# uC.net
KiCad netlist of a schematic drawn in Altium Designer
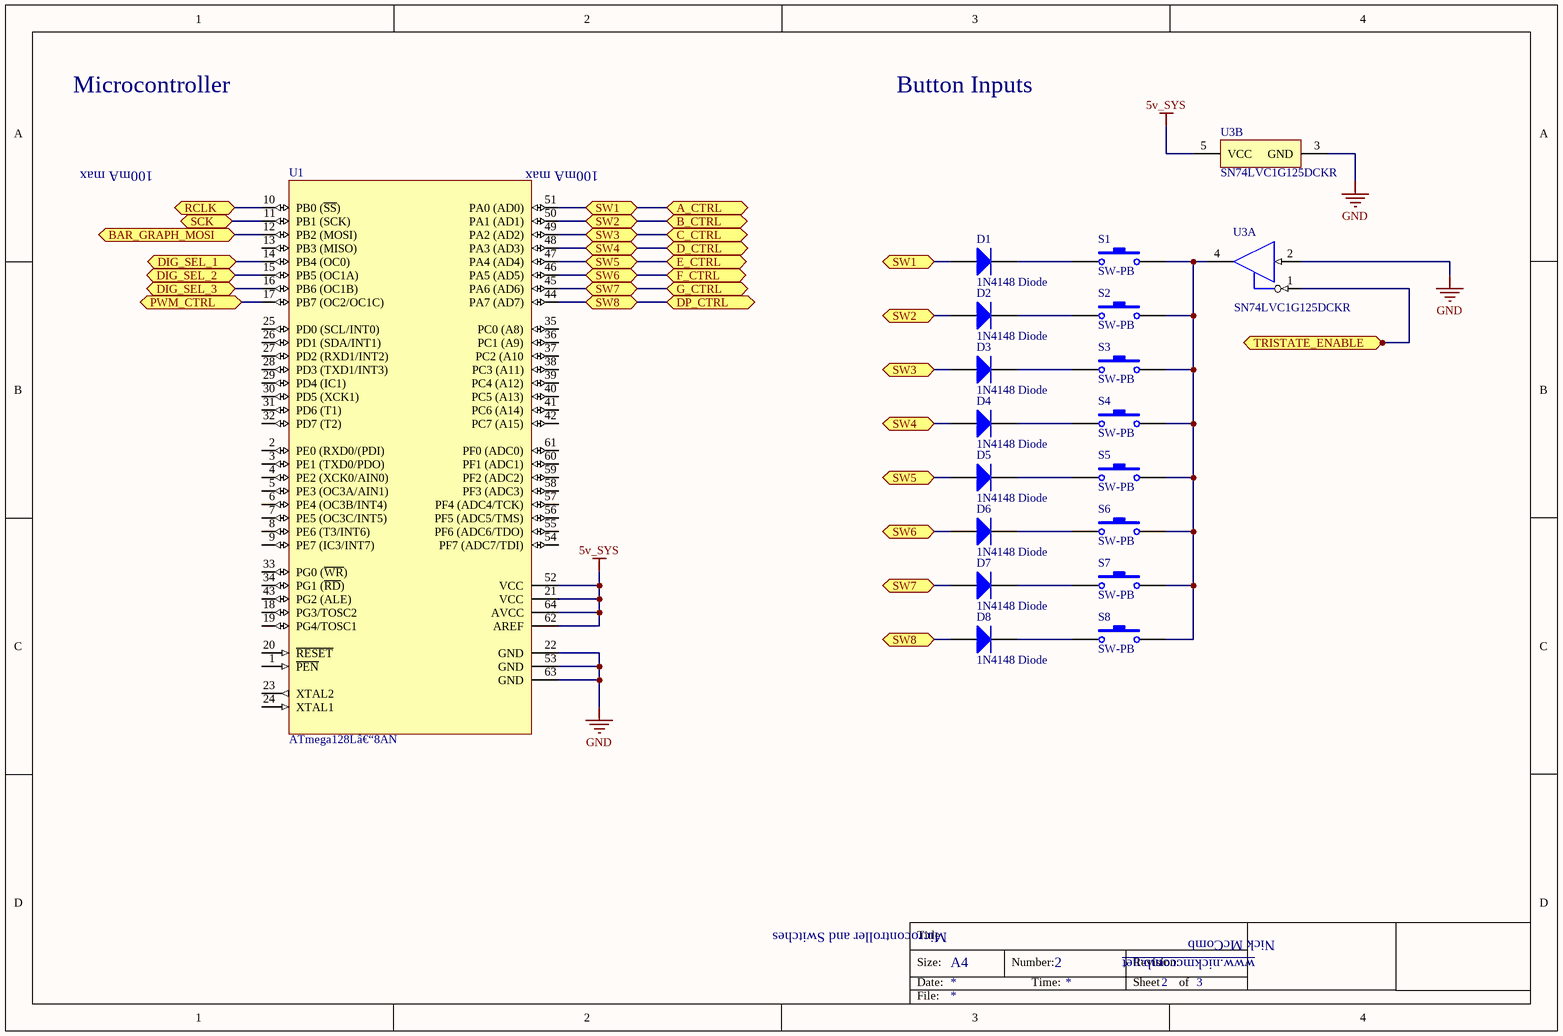
[diagram p0: uC.SchDoc]

(export (version "E")
  (design (tool "Eeschema 10.0.6"))
  (components
    (comp (ref "D1")
      (value "1N4148 Diode")
      (footprint "S01575 Diode")
      (description "Diode")
      (libsource (lib "lab2") (part "Diode"))
    )
    (comp (ref "D2")
      (value "1N4148 Diode")
      (footprint "S01575 Diode")
      (description "Diode")
      (libsource (lib "lab2") (part "Diode"))
    )
    (comp (ref "D3")
      (value "1N4148 Diode")
      (footprint "S01575 Diode")
      (description "Diode")
      (libsource (lib "lab2") (part "Diode"))
    )
    (comp (ref "D4")
      (value "1N4148 Diode")
      (footprint "S01575 Diode")
      (description "Diode")
      (libsource (lib "lab2") (part "Diode"))
    )
    (comp (ref "D5")
      (value "1N4148 Diode")
      (footprint "S01575 Diode")
      (description "Diode")
      (libsource (lib "lab2") (part "Diode"))
    )
    (comp (ref "D6")
      (value "1N4148 Diode")
      (footprint "S01575 Diode")
      (description "Diode")
      (libsource (lib "lab2") (part "Diode"))
    )
    (comp (ref "D7")
      (value "1N4148 Diode")
      (footprint "S01575 Diode")
      (description "Diode")
      (libsource (lib "lab2") (part "Diode"))
    )
    (comp (ref "D8")
      (value "1N4148 Diode")
      (footprint "S01575 Diode")
      (description "Diode")
      (libsource (lib "lab2") (part "Diode"))
    )
    (comp (ref "S1")
      (value "SW-PB")
      (footprint "SW-PB")
      (description "Switch")
      (libsource (lib "lab2") (part "SW-PB"))
    )
    (comp (ref "S2")
      (value "SW-PB")
      (footprint "SW-PB")
      (description "Switch")
      (libsource (lib "lab2") (part "SW-PB"))
    )
    (comp (ref "S3")
      (value "SW-PB")
      (footprint "SW-PB")
      (description "Switch")
      (libsource (lib "lab2") (part "SW-PB"))
    )
    (comp (ref "S4")
      (value "SW-PB")
      (footprint "SW-PB")
      (description "Switch")
      (libsource (lib "lab2") (part "SW-PB"))
    )
    (comp (ref "S5")
      (value "SW-PB")
      (footprint "SW-PB")
      (description "Switch")
      (libsource (lib "lab2") (part "SW-PB"))
    )
    (comp (ref "S6")
      (value "SW-PB")
      (footprint "SW-PB")
      (description "Switch")
      (libsource (lib "lab2") (part "SW-PB"))
    )
    (comp (ref "S7")
      (value "SW-PB")
      (footprint "SW-PB")
      (description "Switch")
      (libsource (lib "lab2") (part "SW-PB"))
    )
    (comp (ref "S8")
      (value "SW-PB")
      (footprint "SW-PB")
      (description "Switch")
      (libsource (lib "lab2") (part "SW-PB"))
    )
    (comp (ref "U1")
      (value "ATmega128Lâ€“8AN")
      (footprint "64A_M")
      (libsource (lib "Altium Content Vault") (part "MC-8B-AT64-SQ64"))
    )
    (comp (ref "U3")
      (value "SN74LVC1G125DCKR")
      (footprint "DCK0005A_M")
      (description "Single Bus Buffer Gate With 3-State Outputs, DCK0005A, LARGE T&R")
      (fields
        (field (name "GENERIC PART NUMBER") "SN74LVC1G125")
        (field (name "MANUFACTURER") "Texas Instruments")
      )
      (libsource (lib "Altium Content Vault") (part "TI-SN74AXXXX1X125-5"))
    )
  )
  (nets
    (net (code "1") (name "/A_CTRL") (class "Default")
      (node (ref "D1") (pin "3") (pinfunction "A_3") (pintype "passive"))
      (node (ref "U1") (pin "51") (pinfunction "PA0_(AD0)_51") (pintype "bidirectional"))
    )
    (net (code "2") (name "/BAR_GRAPH_MOSI") (class "Default")
      (node (ref "U1") (pin "12") (pinfunction "PB2_(MOSI)_12") (pintype "bidirectional"))
    )
    (net (code "3") (name "/B_CTRL") (class "Default")
      (node (ref "D2") (pin "3") (pinfunction "A_3") (pintype "passive"))
      (node (ref "U1") (pin "50") (pinfunction "PA1_(AD1)_50") (pintype "bidirectional"))
    )
    (net (code "4") (name "/C_CTRL") (class "Default")
      (node (ref "D3") (pin "3") (pinfunction "A_3") (pintype "passive"))
      (node (ref "U1") (pin "49") (pinfunction "PA2_(AD2)_49") (pintype "bidirectional"))
    )
    (net (code "5") (name "/DIG_SEL_1") (class "Default")
      (node (ref "U1") (pin "14") (pinfunction "PB4_(OC0)_14") (pintype "bidirectional"))
    )
    (net (code "6") (name "/DIG_SEL_2") (class "Default")
      (node (ref "U1") (pin "15") (pinfunction "PB5_(OC1A)_15") (pintype "bidirectional"))
    )
    (net (code "7") (name "/DIG_SEL_3") (class "Default")
      (node (ref "U1") (pin "16") (pinfunction "PB6_(OC1B)_16") (pintype "bidirectional"))
    )
    (net (code "8") (name "/DP_CTRL") (class "Default")
      (node (ref "D8") (pin "3") (pinfunction "A_3") (pintype "passive"))
      (node (ref "U1") (pin "44") (pinfunction "PA7_(AD7)_44") (pintype "bidirectional"))
    )
    (net (code "9") (name "/D_CTRL") (class "Default")
      (node (ref "D4") (pin "3") (pinfunction "A_3") (pintype "passive"))
      (node (ref "U1") (pin "48") (pinfunction "PA3_(AD3)_48") (pintype "bidirectional"))
    )
    (net (code "10") (name "/E_CTRL") (class "Default")
      (node (ref "D5") (pin "3") (pinfunction "A_3") (pintype "passive"))
      (node (ref "U1") (pin "47") (pinfunction "PA4_(AD4)_47") (pintype "bidirectional"))
    )
    (net (code "11") (name "/F_CTRL") (class "Default")
      (node (ref "D6") (pin "3") (pinfunction "A_3") (pintype "passive"))
      (node (ref "U1") (pin "46") (pinfunction "PA5_(AD5)_46") (pintype "bidirectional"))
    )
    (net (code "12") (name "/G_CTRL") (class "Default")
      (node (ref "D7") (pin "3") (pinfunction "A_3") (pintype "passive"))
      (node (ref "U1") (pin "45") (pinfunction "PA6_(AD6)_45") (pintype "bidirectional"))
    )
    (net (code "13") (name "/PWM_CTRL") (class "Default")
      (node (ref "U1") (pin "17") (pinfunction "PB7_(OC2/OC1C)_17") (pintype "bidirectional"))
    )
    (net (code "14") (name "/RCLK") (class "Default")
      (node (ref "U1") (pin "10") (pinfunction "PB0_(~{SS})_10") (pintype "bidirectional"))
    )
    (net (code "15") (name "/SCK") (class "Default")
      (node (ref "U1") (pin "11") (pinfunction "PB1_(SCK)_11") (pintype "bidirectional"))
    )
    (net (code "16") (name "/TRISTATE_ENABLE") (class "Default")
      (node (ref "U3") (pin "1") (pinfunction "~{OE}_1") (pintype "input"))
    )
    (net (code "17") (name "5v_SYS") (class "Default")
      (node (ref "U1") (pin "21") (pinfunction "VCC_21") (pintype "power_in"))
      (node (ref "U1") (pin "52") (pinfunction "VCC_52") (pintype "power_in"))
      (node (ref "U1") (pin "62") (pinfunction "AREF_62") (pintype "passive"))
      (node (ref "U1") (pin "64") (pinfunction "AVCC_64") (pintype "power_in"))
      (node (ref "U3") (pin "5") (pinfunction "VCC_5") (pintype "power_in"))
    )
    (net (code "18") (name "GND") (class "Default")
      (node (ref "U1") (pin "22") (pinfunction "GND_22") (pintype "power_in"))
      (node (ref "U1") (pin "53") (pinfunction "GND_53") (pintype "power_in"))
      (node (ref "U1") (pin "63") (pinfunction "GND_63") (pintype "power_in"))
      (node (ref "U3") (pin "2") (pinfunction "A_2") (pintype "input"))
      (node (ref "U3") (pin "3") (pinfunction "GND_3") (pintype "power_in"))
    )
    (net (code "19") (name "Net-(D1-K)") (class "Default")
      (node (ref "D1") (pin "1") (pinfunction "K_1") (pintype "passive"))
      (node (ref "S1") (pin "1") (pinfunction "1_1") (pintype "passive"))
    )
    (net (code "20") (name "Net-(D2-K)") (class "Default")
      (node (ref "D2") (pin "1") (pinfunction "K_1") (pintype "passive"))
      (node (ref "S2") (pin "1") (pinfunction "1_1") (pintype "passive"))
    )
    (net (code "21") (name "Net-(D3-K)") (class "Default")
      (node (ref "D3") (pin "1") (pinfunction "K_1") (pintype "passive"))
      (node (ref "S3") (pin "1") (pinfunction "1_1") (pintype "passive"))
    )
    (net (code "22") (name "Net-(D4-K)") (class "Default")
      (node (ref "D4") (pin "1") (pinfunction "K_1") (pintype "passive"))
      (node (ref "S4") (pin "1") (pinfunction "1_1") (pintype "passive"))
    )
    (net (code "23") (name "Net-(D5-K)") (class "Default")
      (node (ref "D5") (pin "1") (pinfunction "K_1") (pintype "passive"))
      (node (ref "S5") (pin "1") (pinfunction "1_1") (pintype "passive"))
    )
    (net (code "24") (name "Net-(D6-K)") (class "Default")
      (node (ref "D6") (pin "1") (pinfunction "K_1") (pintype "passive"))
      (node (ref "S6") (pin "1") (pinfunction "1_1") (pintype "passive"))
    )
    (net (code "25") (name "Net-(D7-K)") (class "Default")
      (node (ref "D7") (pin "1") (pinfunction "K_1") (pintype "passive"))
      (node (ref "S7") (pin "1") (pinfunction "1_1") (pintype "passive"))
    )
    (net (code "26") (name "Net-(D8-K)") (class "Default")
      (node (ref "D8") (pin "1") (pinfunction "K_1") (pintype "passive"))
      (node (ref "S8") (pin "1") (pinfunction "1_1") (pintype "passive"))
    )
    (net (code "27") (name "Net-(U3A-Y)") (class "Default")
      (node (ref "S1") (pin "2") (pinfunction "2_2") (pintype "passive"))
      (node (ref "S2") (pin "2") (pinfunction "2_2") (pintype "passive"))
      (node (ref "S3") (pin "2") (pinfunction "2_2") (pintype "passive"))
      (node (ref "S4") (pin "2") (pinfunction "2_2") (pintype "passive"))
      (node (ref "S5") (pin "2") (pinfunction "2_2") (pintype "passive"))
      (node (ref "S6") (pin "2") (pinfunction "2_2") (pintype "passive"))
      (node (ref "S7") (pin "2") (pinfunction "2_2") (pintype "passive"))
      (node (ref "S8") (pin "2") (pinfunction "2_2") (pintype "passive"))
      (node (ref "U3") (pin "4") (pinfunction "Y_4") (pintype "tri_state"))
    )
    (net (code "28") (name "unconnected-(U1-PB3_(MISO)-Pad13)") (class "Default")
      (node (ref "U1") (pin "13") (pinfunction "PB3_(MISO)_13") (pintype "bidirectional"))
    )
    (net (code "29") (name "unconnected-(U1-PC0_(A8)-Pad35)") (class "Default")
      (node (ref "U1") (pin "35") (pinfunction "PC0_(A8)_35") (pintype "bidirectional"))
    )
    (net (code "30") (name "unconnected-(U1-PC1_(A9)-Pad36)") (class "Default")
      (node (ref "U1") (pin "36") (pinfunction "PC1_(A9)_36") (pintype "bidirectional"))
    )
    (net (code "31") (name "unconnected-(U1-PC2_(A10-Pad37)") (class "Default")
      (node (ref "U1") (pin "37") (pinfunction "PC2_(A10_37") (pintype "bidirectional"))
    )
    (net (code "32") (name "unconnected-(U1-PC3_(A11)-Pad38)") (class "Default")
      (node (ref "U1") (pin "38") (pinfunction "PC3_(A11)_38") (pintype "bidirectional"))
    )
    (net (code "33") (name "unconnected-(U1-PC4_(A12)-Pad39)") (class "Default")
      (node (ref "U1") (pin "39") (pinfunction "PC4_(A12)_39") (pintype "bidirectional"))
    )
    (net (code "34") (name "unconnected-(U1-PC5_(A13)-Pad40)") (class "Default")
      (node (ref "U1") (pin "40") (pinfunction "PC5_(A13)_40") (pintype "bidirectional"))
    )
    (net (code "35") (name "unconnected-(U1-PC6_(A14)-Pad41)") (class "Default")
      (node (ref "U1") (pin "41") (pinfunction "PC6_(A14)_41") (pintype "bidirectional"))
    )
    (net (code "36") (name "unconnected-(U1-PC7_(A15)-Pad42)") (class "Default")
      (node (ref "U1") (pin "42") (pinfunction "PC7_(A15)_42") (pintype "bidirectional"))
    )
    (net (code "37") (name "unconnected-(U1-PD0_(SCL{slash}INT0)-Pad25)") (class "Default")
      (node (ref "U1") (pin "25") (pinfunction "PD0_(SCL/INT0)_25") (pintype "bidirectional"))
    )
    (net (code "38") (name "unconnected-(U1-PD1_(SDA{slash}INT1)-Pad26)") (class "Default")
      (node (ref "U1") (pin "26") (pinfunction "PD1_(SDA/INT1)_26") (pintype "bidirectional"))
    )
    (net (code "39") (name "unconnected-(U1-PD2_(RXD1{slash}INT2)-Pad27)") (class "Default")
      (node (ref "U1") (pin "27") (pinfunction "PD2_(RXD1/INT2)_27") (pintype "bidirectional"))
    )
    (net (code "40") (name "unconnected-(U1-PD3_(TXD1{slash}INT3)-Pad28)") (class "Default")
      (node (ref "U1") (pin "28") (pinfunction "PD3_(TXD1/INT3)_28") (pintype "bidirectional"))
    )
    (net (code "41") (name "unconnected-(U1-PD4_(IC1)-Pad29)") (class "Default")
      (node (ref "U1") (pin "29") (pinfunction "PD4_(IC1)_29") (pintype "bidirectional"))
    )
    (net (code "42") (name "unconnected-(U1-PD5_(XCK1)-Pad30)") (class "Default")
      (node (ref "U1") (pin "30") (pinfunction "PD5_(XCK1)_30") (pintype "bidirectional"))
    )
    (net (code "43") (name "unconnected-(U1-PD6_(T1)-Pad31)") (class "Default")
      (node (ref "U1") (pin "31") (pinfunction "PD6_(T1)_31") (pintype "bidirectional"))
    )
    (net (code "44") (name "unconnected-(U1-PD7_(T2)-Pad32)") (class "Default")
      (node (ref "U1") (pin "32") (pinfunction "PD7_(T2)_32") (pintype "bidirectional"))
    )
    (net (code "45") (name "unconnected-(U1-PE0_(RXD0{slash}(PDI)-Pad2)") (class "Default")
      (node (ref "U1") (pin "2") (pinfunction "PE0_(RXD0/(PDI)_2") (pintype "bidirectional"))
    )
    (net (code "46") (name "unconnected-(U1-PE1_(TXD0{slash}PDO)-Pad3)") (class "Default")
      (node (ref "U1") (pin "3") (pinfunction "PE1_(TXD0/PDO)_3") (pintype "bidirectional"))
    )
    (net (code "47") (name "unconnected-(U1-PE2_(XCK0{slash}AIN0)-Pad4)") (class "Default")
      (node (ref "U1") (pin "4") (pinfunction "PE2_(XCK0/AIN0)_4") (pintype "bidirectional"))
    )
    (net (code "48") (name "unconnected-(U1-PE3_(OC3A{slash}AIN1)-Pad5)") (class "Default")
      (node (ref "U1") (pin "5") (pinfunction "PE3_(OC3A/AIN1)_5") (pintype "bidirectional"))
    )
    (net (code "49") (name "unconnected-(U1-PE4_(OC3B{slash}INT4)-Pad6)") (class "Default")
      (node (ref "U1") (pin "6") (pinfunction "PE4_(OC3B/INT4)_6") (pintype "bidirectional"))
    )
    (net (code "50") (name "unconnected-(U1-PE5_(OC3C{slash}INT5)-Pad7)") (class "Default")
      (node (ref "U1") (pin "7") (pinfunction "PE5_(OC3C/INT5)_7") (pintype "bidirectional"))
    )
    (net (code "51") (name "unconnected-(U1-PE6_(T3{slash}INT6)-Pad8)") (class "Default")
      (node (ref "U1") (pin "8") (pinfunction "PE6_(T3/INT6)_8") (pintype "bidirectional"))
    )
    (net (code "52") (name "unconnected-(U1-PE7_(IC3{slash}INT7)-Pad9)") (class "Default")
      (node (ref "U1") (pin "9") (pinfunction "PE7_(IC3/INT7)_9") (pintype "bidirectional"))
    )
    (net (code "53") (name "unconnected-(U1-PF0_(ADC0)-Pad61)") (class "Default")
      (node (ref "U1") (pin "61") (pinfunction "PF0_(ADC0)_61") (pintype "bidirectional"))
    )
    (net (code "54") (name "unconnected-(U1-PF1_(ADC1)-Pad60)") (class "Default")
      (node (ref "U1") (pin "60") (pinfunction "PF1_(ADC1)_60") (pintype "bidirectional"))
    )
    (net (code "55") (name "unconnected-(U1-PF2_(ADC2)-Pad59)") (class "Default")
      (node (ref "U1") (pin "59") (pinfunction "PF2_(ADC2)_59") (pintype "bidirectional"))
    )
    (net (code "56") (name "unconnected-(U1-PF3_(ADC3)-Pad58)") (class "Default")
      (node (ref "U1") (pin "58") (pinfunction "PF3_(ADC3)_58") (pintype "bidirectional"))
    )
    (net (code "57") (name "unconnected-(U1-PF4_(ADC4{slash}TCK)-Pad57)") (class "Default")
      (node (ref "U1") (pin "57") (pinfunction "PF4_(ADC4/TCK)_57") (pintype "bidirectional"))
    )
    (net (code "58") (name "unconnected-(U1-PF5_(ADC5{slash}TMS)-Pad56)") (class "Default")
      (node (ref "U1") (pin "56") (pinfunction "PF5_(ADC5/TMS)_56") (pintype "bidirectional"))
    )
    (net (code "59") (name "unconnected-(U1-PF6_(ADC6{slash}TDO)-Pad55)") (class "Default")
      (node (ref "U1") (pin "55") (pinfunction "PF6_(ADC6/TDO)_55") (pintype "bidirectional"))
    )
    (net (code "60") (name "unconnected-(U1-PF7_(ADC7{slash}TDI)-Pad54)") (class "Default")
      (node (ref "U1") (pin "54") (pinfunction "PF7_(ADC7/TDI)_54") (pintype "bidirectional"))
    )
    (net (code "61") (name "unconnected-(U1-PG0_(~{WR})-Pad33)") (class "Default")
      (node (ref "U1") (pin "33") (pinfunction "PG0_(~{WR})_33") (pintype "bidirectional"))
    )
    (net (code "62") (name "unconnected-(U1-PG1_(~{RD})-Pad34)") (class "Default")
      (node (ref "U1") (pin "34") (pinfunction "PG1_(~{RD})_34") (pintype "bidirectional"))
    )
    (net (code "63") (name "unconnected-(U1-PG2_(ALE)-Pad43)") (class "Default")
      (node (ref "U1") (pin "43") (pinfunction "PG2_(ALE)_43") (pintype "bidirectional"))
    )
    (net (code "64") (name "unconnected-(U1-PG3{slash}TOSC2-Pad18)") (class "Default")
      (node (ref "U1") (pin "18") (pinfunction "PG3/TOSC2_18") (pintype "bidirectional"))
    )
    (net (code "65") (name "unconnected-(U1-PG4{slash}TOSC1-Pad19)") (class "Default")
      (node (ref "U1") (pin "19") (pinfunction "PG4/TOSC1_19") (pintype "bidirectional"))
    )
    (net (code "66") (name "unconnected-(U1-XTAL1-Pad24)") (class "Default")
      (node (ref "U1") (pin "24") (pinfunction "XTAL1_24") (pintype "input"))
    )
    (net (code "67") (name "unconnected-(U1-XTAL2-Pad23)") (class "Default")
      (node (ref "U1") (pin "23") (pinfunction "XTAL2_23") (pintype "output"))
    )
    (net (code "68") (name "unconnected-(U1-~{PEN}-Pad1)") (class "Default")
      (node (ref "U1") (pin "1") (pinfunction "~{PEN}_1") (pintype "input"))
    )
    (net (code "69") (name "unconnected-(U1-~{RESET}-Pad20)") (class "Default")
      (node (ref "U1") (pin "20") (pinfunction "~{RESET}_20") (pintype "input"))
    )
  )
)
